# CtDSP_IO.net
KiCad netlist of a schematic drawn in Altium Designer
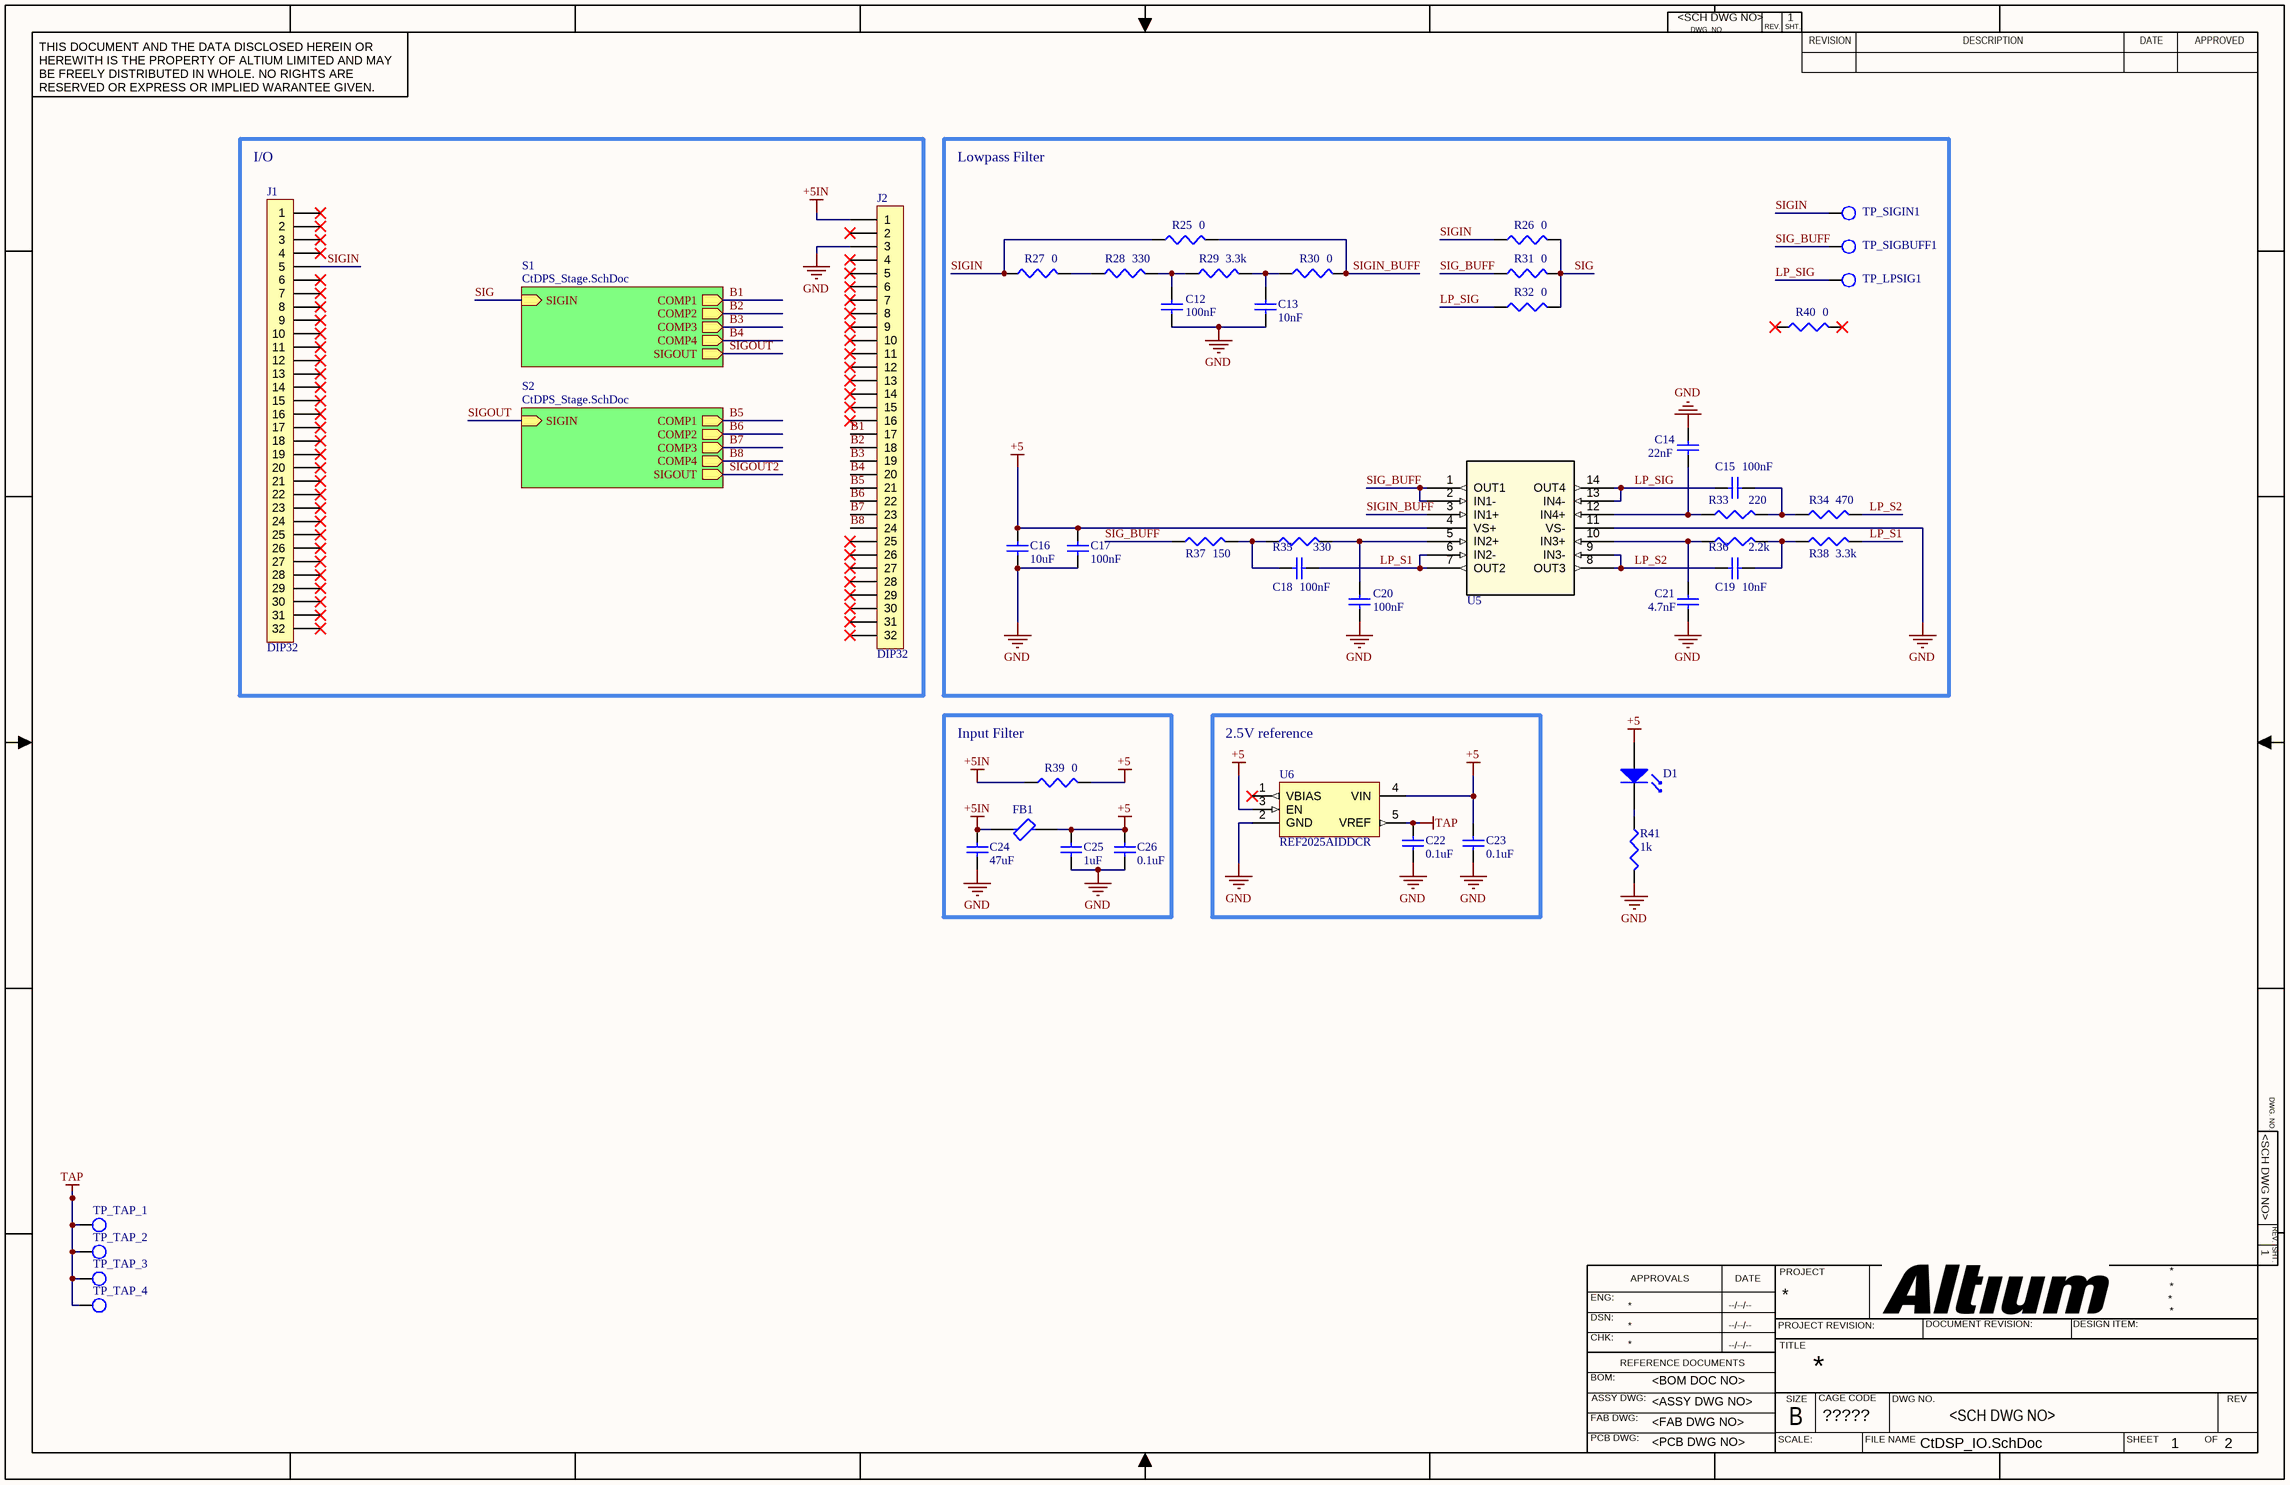
[diagram p0: CtDSP_IO.SchDoc]

(export (version "E")
  (design (tool "Eeschema 10.0.6"))
  (components
    (comp (ref "C12")
      (value "100nF")
      (footprint "C_0402")
      (fields (field (name "LCSC PART #") "C1525"))
      (libsource (lib "ctdsp") (part "C_0402"))
    )
    (comp (ref "C13")
      (value "10nF")
      (footprint "C_0402")
      (fields (field (name "LCSC PART #") "C15195"))
      (libsource (lib "ctdsp") (part "C_0402"))
    )
    (comp (ref "C14")
      (value "22nF")
      (footprint "C_0402")
      (fields (field (name "LCSC PART #") "C1532"))
      (libsource (lib "ctdsp") (part "C_0402"))
    )
    (comp (ref "C15")
      (value "100nF")
      (footprint "C_0402")
      (fields (field (name "LCSC PART #") "C1525"))
      (libsource (lib "ctdsp") (part "C_0402"))
    )
    (comp (ref "C16")
      (value "10uF")
      (footprint "C_0402")
      (fields (field (name "LCSC PART #") "C15525"))
      (libsource (lib "ctdsp") (part "C_0402"))
    )
    (comp (ref "C17")
      (value "100nF")
      (footprint "C_0402")
      (fields (field (name "LCSC PART #") "C1525"))
      (libsource (lib "ctdsp") (part "C_0402"))
    )
    (comp (ref "C18")
      (value "100nF")
      (footprint "C_0402")
      (fields (field (name "LCSC PART #") "C1525"))
      (libsource (lib "ctdsp") (part "C_0402"))
    )
    (comp (ref "C19")
      (value "10nF")
      (footprint "C_0402")
      (fields (field (name "LCSC PART #") "C15195"))
      (libsource (lib "ctdsp") (part "C_0402"))
    )
    (comp (ref "C20")
      (value "100nF")
      (footprint "C_0402")
      (fields (field (name "LCSC PART #") "C1525"))
      (libsource (lib "ctdsp") (part "C_0402"))
    )
    (comp (ref "C21")
      (value "4.7nF")
      (footprint "C_0402")
      (fields (field (name "LCSC PART #") "C1538"))
      (libsource (lib "ctdsp") (part "C_0402"))
    )
    (comp (ref "C22")
      (value "0.1uF")
      (footprint "C_0402")
      (fields (field (name "LCSC PART #") "C1525"))
      (libsource (lib "ctdsp") (part "C_0402"))
    )
    (comp (ref "C23")
      (value "0.1uF")
      (footprint "C_0402")
      (fields (field (name "LCSC PART #") "C1525"))
      (libsource (lib "ctdsp") (part "C_0402"))
    )
    (comp (ref "C24")
      (value "47uF")
      (footprint "C_0805")
      (fields (field (name "LCSC PART #") "C16780"))
      (libsource (lib "ctdsp") (part "C_0805"))
    )
    (comp (ref "C25")
      (value "1uF")
      (footprint "C_0603")
      (fields (field (name "LCSC PART #") "C15849"))
      (libsource (lib "ctdsp") (part "C_0603"))
    )
    (comp (ref "C26")
      (value "0.1uF")
      (footprint "C_0402")
      (fields (field (name "LCSC PART #") "C1525"))
      (libsource (lib "ctdsp") (part "C_0402"))
    )
    (comp (ref "D1")
      (value "LED_0603")
      (footprint "LED_6003")
      (fields (field (name "LCSC PART #") "C2286"))
      (libsource (lib "ctdsp") (part "LED_0603"))
    )
    (comp (ref "FB1")
      (value "BLM18PG121SN1D")
      (footprint "BLM18PG121SN1D")
      (description "-55℃~+125℃ 1 120Ω@100MHz 2A 50mΩ ±25% 0603 Ferrite Beads ROHS")
      (fields (field (name "LCSC PART #") "C14709"))
      (libsource (lib "ctdsp") (part "BLM18PG121SN1D"))
    )
    (comp (ref "J1") (value "DIP32") (footprint "DIP32") (libsource (lib "ctdsp") (part "DIP32")))
    (comp (ref "J2") (value "DIP32") (footprint "DIP32") (libsource (lib "") (part "DIP32_1")))
    (comp (ref "R25")
      (value "0")
      (footprint "RES_1206")
      (fields (field (name "LCSC PART #") "C17888"))
      (libsource (lib "ctdsp") (part "RES_1206"))
    )
    (comp (ref "R26")
      (value "0")
      (footprint "RES_1206")
      (fields (field (name "LCSC PART #") "C17888"))
      (libsource (lib "ctdsp") (part "RES_1206"))
    )
    (comp (ref "R27")
      (value "0")
      (footprint "RES_1206")
      (fields (field (name "LCSC PART #") "C17888"))
      (libsource (lib "ctdsp") (part "RES_1206"))
    )
    (comp (ref "R28")
      (value "330")
      (footprint "RES_0603")
      (fields (field (name "LCSC PART #") "C23138"))
      (libsource (lib "ctdsp") (part "RES_0603"))
    )
    (comp (ref "R29")
      (value "3.3k")
      (footprint "RES_0603")
      (fields (field (name "LCSC PART #") "C22978"))
      (libsource (lib "ctdsp") (part "RES_0603"))
    )
    (comp (ref "R30")
      (value "0")
      (footprint "RES_1206")
      (fields (field (name "LCSC PART #") "C17888"))
      (libsource (lib "ctdsp") (part "RES_1206"))
    )
    (comp (ref "R31")
      (value "0")
      (footprint "RES_1206")
      (fields (field (name "LCSC PART #") "C17888"))
      (libsource (lib "ctdsp") (part "RES_1206"))
    )
    (comp (ref "R32")
      (value "0")
      (footprint "RES_1206")
      (fields (field (name "LCSC PART #") "C17888"))
      (libsource (lib "ctdsp") (part "RES_1206"))
    )
    (comp (ref "R33")
      (value "220")
      (footprint "RES_0402")
      (fields (field (name "LCSC PART #") "C25091"))
      (libsource (lib "ctdsp") (part "RES_0402"))
    )
    (comp (ref "R34")
      (value "470")
      (footprint "RES_0402")
      (fields (field (name "LCSC PART #") "C25117"))
      (libsource (lib "ctdsp") (part "RES_0402"))
    )
    (comp (ref "R35")
      (value "330")
      (footprint "RES_0603")
      (fields (field (name "LCSC PART #") "C23138"))
      (libsource (lib "ctdsp") (part "RES_0603"))
    )
    (comp (ref "R36")
      (value "2.2k")
      (footprint "RES_0603")
      (fields (field (name "LCSC PART #") "C4190"))
      (libsource (lib "ctdsp") (part "RES_0603"))
    )
    (comp (ref "R37")
      (value "150")
      (footprint "RES_0603")
      (fields (field (name "LCSC PART #") "C22808"))
      (libsource (lib "ctdsp") (part "RES_0603"))
    )
    (comp (ref "R38")
      (value "3.3k")
      (footprint "RES_0603")
      (fields (field (name "LCSC PART #") "C22978"))
      (libsource (lib "ctdsp") (part "RES_0603"))
    )
    (comp (ref "R39")
      (value "0")
      (footprint "RES_1206")
      (fields (field (name "LCSC PART #") "C17888"))
      (libsource (lib "ctdsp") (part "RES_1206"))
    )
    (comp (ref "R40")
      (value "0")
      (footprint "RES_1206")
      (fields (field (name "LCSC PART #") "C17888"))
      (libsource (lib "ctdsp") (part "RES_1206"))
    )
    (comp (ref "R41")
      (value "1k")
      (footprint "RES_0402")
      (fields (field (name "LCSC PART #") "C11702"))
      (libsource (lib "ctdsp") (part "RES_0402"))
    )
    (comp (ref "TP_LPSIG1")
      (value "TESTPOINT")
      (footprint "TESTPOINT")
      (libsource (lib "ctdsp") (part "TESTPOINT"))
    )
    (comp (ref "TP_SIGBUFF1")
      (value "TESTPOINT")
      (footprint "TESTPOINT")
      (libsource (lib "ctdsp") (part "TESTPOINT"))
    )
    (comp (ref "TP_SIGIN1")
      (value "TESTPOINT")
      (footprint "TESTPOINT")
      (libsource (lib "ctdsp") (part "TESTPOINT"))
    )
    (comp (ref "TP_TAP_1")
      (value "TESTPOINT")
      (footprint "TESTPOINT")
      (libsource (lib "ctdsp") (part "TESTPOINT"))
    )
    (comp (ref "TP_TAP_2")
      (value "TESTPOINT")
      (footprint "TESTPOINT")
      (libsource (lib "ctdsp") (part "TESTPOINT"))
    )
    (comp (ref "TP_TAP_3")
      (value "TESTPOINT")
      (footprint "TESTPOINT")
      (libsource (lib "ctdsp") (part "TESTPOINT"))
    )
    (comp (ref "TP_TAP_4")
      (value "TP_TAP_4")
      (footprint "TESTPOINT")
      (libsource (lib "ctdsp") (part "TESTPOINT"))
    )
    (comp (ref "U5")
      (value "ADA4891-4ARZ-R7")
      (footprint "ADA4891-4ARZ-R7")
      (description "Quad Rail-to-Rail Op-Amp, 240 MHz, 170 V/µs, SOT-23-5")
      (fields (field (name "LCSC PART #") "C654290"))
      (libsource (lib "ctdsp") (part "ADA4891-4ARZ-R7"))
    )
    (comp (ref "U6")
      (value "REF2025AIDDCR")
      (footprint "REF2025AIDDCR")
      (fields (field (name "LCSC PART #") "C962078"))
      (libsource (lib "ctdsp") (part "REF2025AIDDCR"))
    )
  )
  (nets
    (net (code "1") (name "+5") (class "Default")
      (node (ref "C16") (pin "1") (pinfunction "1_1") (pintype "passive"))
      (node (ref "C17") (pin "2") (pinfunction "2_2") (pintype "passive"))
      (node (ref "C23") (pin "1") (pinfunction "1_1") (pintype "passive"))
      (node (ref "C25") (pin "2") (pinfunction "2_2") (pintype "passive"))
      (node (ref "C26") (pin "1") (pinfunction "1_1") (pintype "passive"))
      (node (ref "D1") (pin "2") (pinfunction "K_2") (pintype "passive"))
      (node (ref "FB1") (pin "2") (pinfunction "2_2") (pintype "passive"))
      (node (ref "R39") (pin "2") (pinfunction "2_2") (pintype "passive"))
      (node (ref "U5") (pin "4") (pinfunction "VS+_4") (pintype "power_in"))
      (node (ref "U6") (pin "3") (pinfunction "EN_3") (pintype "input"))
      (node (ref "U6") (pin "4") (pinfunction "VIN_4") (pintype "power_in"))
    )
    (net (code "2") (name "+5IN") (class "Default")
      (node (ref "C24") (pin "2") (pinfunction "2_2") (pintype "passive"))
      (node (ref "FB1") (pin "1") (pinfunction "1_1") (pintype "passive"))
      (node (ref "J2") (pin "1") (pinfunction "1_1") (pintype "passive"))
      (node (ref "R39") (pin "1") (pinfunction "1_1") (pintype "passive"))
    )
    (net (code "3") (name "/B1") (class "Default")
      (node (ref "J2") (pin "17") (pinfunction "17_17") (pintype "passive"))
    )
    (net (code "4") (name "/B2") (class "Default")
      (node (ref "J2") (pin "18") (pinfunction "18_18") (pintype "passive"))
    )
    (net (code "5") (name "/B3") (class "Default")
      (node (ref "J2") (pin "19") (pinfunction "19_19") (pintype "passive"))
    )
    (net (code "6") (name "/B4") (class "Default")
      (node (ref "J2") (pin "20") (pinfunction "20_20") (pintype "passive"))
    )
    (net (code "7") (name "/B5") (class "Default")
      (node (ref "J2") (pin "21") (pinfunction "21_21") (pintype "passive"))
    )
    (net (code "8") (name "/B6") (class "Default")
      (node (ref "J2") (pin "22") (pinfunction "22_22") (pintype "passive"))
    )
    (net (code "9") (name "/B7") (class "Default")
      (node (ref "J2") (pin "23") (pinfunction "23_23") (pintype "passive"))
    )
    (net (code "10") (name "/B8") (class "Default")
      (node (ref "J2") (pin "24") (pinfunction "24_24") (pintype "passive"))
    )
    (net (code "11") (name "/LP_S1") (class "Default")
      (node (ref "C18") (pin "1") (pinfunction "1_1") (pintype "passive"))
      (node (ref "R38") (pin "2") (pinfunction "2_2") (pintype "passive"))
      (node (ref "U5") (pin "6") (pinfunction "IN2-_6") (pintype "input"))
      (node (ref "U5") (pin "7") (pinfunction "OUT2_7") (pintype "output"))
    )
    (net (code "12") (name "/LP_S2") (class "Default")
      (node (ref "C19") (pin "1") (pinfunction "1_1") (pintype "passive"))
      (node (ref "R34") (pin "2") (pinfunction "2_2") (pintype "passive"))
      (node (ref "U5") (pin "8") (pinfunction "OUT3_8") (pintype "output"))
      (node (ref "U5") (pin "9") (pinfunction "IN3-_9") (pintype "input"))
    )
    (net (code "13") (name "/LP_SIG") (class "Default")
      (node (ref "C15") (pin "2") (pinfunction "2_2") (pintype "passive"))
      (node (ref "R32") (pin "1") (pinfunction "1_1") (pintype "passive"))
      (node (ref "TP_LPSIG1") (pin "1") (pinfunction "1_1") (pintype "passive"))
      (node (ref "U5") (pin "13") (pinfunction "IN4-_13") (pintype "input"))
      (node (ref "U5") (pin "14") (pinfunction "OUT4_14") (pintype "output"))
    )
    (net (code "14") (name "/SIG") (class "Default")
      (node (ref "R26") (pin "2") (pinfunction "2_2") (pintype "passive"))
      (node (ref "R31") (pin "2") (pinfunction "2_2") (pintype "passive"))
      (node (ref "R32") (pin "2") (pinfunction "2_2") (pintype "passive"))
    )
    (net (code "15") (name "/SIGIN") (class "Default")
      (node (ref "J1") (pin "5") (pinfunction "5_5") (pintype "passive"))
      (node (ref "R25") (pin "1") (pinfunction "1_1") (pintype "passive"))
      (node (ref "R26") (pin "1") (pinfunction "1_1") (pintype "passive"))
      (node (ref "R27") (pin "1") (pinfunction "1_1") (pintype "passive"))
      (node (ref "TP_SIGIN1") (pin "1") (pinfunction "1_1") (pintype "passive"))
    )
    (net (code "16") (name "/SIGIN_BUFF") (class "Default")
      (node (ref "R25") (pin "2") (pinfunction "2_2") (pintype "passive"))
      (node (ref "R30") (pin "2") (pinfunction "2_2") (pintype "passive"))
      (node (ref "U5") (pin "3") (pinfunction "IN1+_3") (pintype "input"))
    )
    (net (code "19") (name "/SIG_BUFF") (class "Default")
      (node (ref "R31") (pin "1") (pinfunction "1_1") (pintype "passive"))
      (node (ref "R37") (pin "1") (pinfunction "1_1") (pintype "passive"))
      (node (ref "TP_SIGBUFF1") (pin "1") (pinfunction "1_1") (pintype "passive"))
      (node (ref "U5") (pin "1") (pinfunction "OUT1_1") (pintype "output"))
      (node (ref "U5") (pin "2") (pinfunction "IN1-_2") (pintype "input"))
    )
    (net (code "20") (name "GND") (class "Default")
      (node (ref "C12") (pin "1") (pinfunction "1_1") (pintype "passive"))
      (node (ref "C13") (pin "1") (pinfunction "1_1") (pintype "passive"))
      (node (ref "C14") (pin "2") (pinfunction "2_2") (pintype "passive"))
      (node (ref "C16") (pin "2") (pinfunction "2_2") (pintype "passive"))
      (node (ref "C17") (pin "1") (pinfunction "1_1") (pintype "passive"))
      (node (ref "C20") (pin "1") (pinfunction "1_1") (pintype "passive"))
      (node (ref "C21") (pin "1") (pinfunction "1_1") (pintype "passive"))
      (node (ref "C22") (pin "2") (pinfunction "2_2") (pintype "passive"))
      (node (ref "C23") (pin "2") (pinfunction "2_2") (pintype "passive"))
      (node (ref "C24") (pin "1") (pinfunction "1_1") (pintype "passive"))
      (node (ref "C25") (pin "1") (pinfunction "1_1") (pintype "passive"))
      (node (ref "C26") (pin "2") (pinfunction "2_2") (pintype "passive"))
      (node (ref "J2") (pin "3") (pinfunction "3_3") (pintype "passive"))
      (node (ref "R41") (pin "2") (pinfunction "2_2") (pintype "passive"))
      (node (ref "U5") (pin "11") (pinfunction "VS-_11") (pintype "power_in"))
      (node (ref "U6") (pin "2") (pinfunction "GND_2") (pintype "power_in"))
    )
    (net (code "21") (name "Net-(C12-Pad2)") (class "Default")
      (node (ref "C12") (pin "2") (pinfunction "2_2") (pintype "passive"))
      (node (ref "R28") (pin "2") (pinfunction "2_2") (pintype "passive"))
      (node (ref "R29") (pin "1") (pinfunction "1_1") (pintype "passive"))
    )
    (net (code "22") (name "Net-(C13-Pad2)") (class "Default")
      (node (ref "C13") (pin "2") (pinfunction "2_2") (pintype "passive"))
      (node (ref "R29") (pin "2") (pinfunction "2_2") (pintype "passive"))
      (node (ref "R30") (pin "1") (pinfunction "1_1") (pintype "passive"))
    )
    (net (code "23") (name "Net-(C15-Pad1)") (class "Default")
      (node (ref "C15") (pin "1") (pinfunction "1_1") (pintype "passive"))
      (node (ref "R33") (pin "2") (pinfunction "2_2") (pintype "passive"))
      (node (ref "R34") (pin "1") (pinfunction "1_1") (pintype "passive"))
    )
    (net (code "24") (name "Net-(C18-Pad2)") (class "Default")
      (node (ref "C18") (pin "2") (pinfunction "2_2") (pintype "passive"))
      (node (ref "R35") (pin "1") (pinfunction "1_1") (pintype "passive"))
      (node (ref "R37") (pin "2") (pinfunction "2_2") (pintype "passive"))
    )
    (net (code "25") (name "Net-(C19-Pad2)") (class "Default")
      (node (ref "C19") (pin "2") (pinfunction "2_2") (pintype "passive"))
      (node (ref "R36") (pin "2") (pinfunction "2_2") (pintype "passive"))
      (node (ref "R38") (pin "1") (pinfunction "1_1") (pintype "passive"))
    )
    (net (code "26") (name "Net-(D1-A)") (class "Default")
      (node (ref "D1") (pin "1") (pinfunction "A_1") (pintype "passive"))
      (node (ref "R41") (pin "1") (pinfunction "1_1") (pintype "passive"))
    )
    (net (code "27") (name "Net-(R27-Pad2)") (class "Default")
      (node (ref "R27") (pin "2") (pinfunction "2_2") (pintype "passive"))
      (node (ref "R28") (pin "1") (pinfunction "1_1") (pintype "passive"))
    )
    (net (code "28") (name "Net-(U5-IN2+)") (class "Default")
      (node (ref "C20") (pin "2") (pinfunction "2_2") (pintype "passive"))
      (node (ref "R35") (pin "2") (pinfunction "2_2") (pintype "passive"))
      (node (ref "U5") (pin "5") (pinfunction "IN2+_5") (pintype "input"))
    )
    (net (code "29") (name "Net-(U5-IN3+)") (class "Default")
      (node (ref "C21") (pin "2") (pinfunction "2_2") (pintype "passive"))
      (node (ref "R36") (pin "1") (pinfunction "1_1") (pintype "passive"))
      (node (ref "U5") (pin "10") (pinfunction "IN3+_10") (pintype "input"))
    )
    (net (code "30") (name "Net-(U5-IN4+)") (class "Default")
      (node (ref "C14") (pin "1") (pinfunction "1_1") (pintype "passive"))
      (node (ref "R33") (pin "1") (pinfunction "1_1") (pintype "passive"))
      (node (ref "U5") (pin "12") (pinfunction "IN4+_12") (pintype "input"))
    )
    (net (code "31") (name "TAP") (class "Default")
      (node (ref "C22") (pin "1") (pinfunction "1_1") (pintype "passive"))
      (node (ref "TP_TAP_1") (pin "1") (pinfunction "1_1") (pintype "passive"))
      (node (ref "TP_TAP_2") (pin "1") (pinfunction "1_1") (pintype "passive"))
      (node (ref "TP_TAP_3") (pin "1") (pinfunction "1_1") (pintype "passive"))
      (node (ref "TP_TAP_4") (pin "1") (pinfunction "1_1") (pintype "passive"))
      (node (ref "U6") (pin "5") (pinfunction "VREF_5") (pintype "output"))
    )
    (net (code "32") (name "unconnected-(J1-Pad1)") (class "Default")
      (node (ref "J1") (pin "1") (pinfunction "1_1") (pintype "passive+no_connect"))
    )
    (net (code "33") (name "unconnected-(J1-Pad2)") (class "Default")
      (node (ref "J1") (pin "2") (pinfunction "2_2") (pintype "passive+no_connect"))
    )
    (net (code "34") (name "unconnected-(J1-Pad3)") (class "Default")
      (node (ref "J1") (pin "3") (pinfunction "3_3") (pintype "passive+no_connect"))
    )
    (net (code "35") (name "unconnected-(J1-Pad4)") (class "Default")
      (node (ref "J1") (pin "4") (pinfunction "4_4") (pintype "passive+no_connect"))
    )
    (net (code "36") (name "unconnected-(J1-Pad6)") (class "Default")
      (node (ref "J1") (pin "6") (pinfunction "6_6") (pintype "passive+no_connect"))
    )
    (net (code "37") (name "unconnected-(J1-Pad7)") (class "Default")
      (node (ref "J1") (pin "7") (pinfunction "7_7") (pintype "passive+no_connect"))
    )
    (net (code "38") (name "unconnected-(J1-Pad8)") (class "Default")
      (node (ref "J1") (pin "8") (pinfunction "8_8") (pintype "passive+no_connect"))
    )
    (net (code "39") (name "unconnected-(J1-Pad9)") (class "Default")
      (node (ref "J1") (pin "9") (pinfunction "9_9") (pintype "passive+no_connect"))
    )
    (net (code "40") (name "unconnected-(J1-Pad10)") (class "Default")
      (node (ref "J1") (pin "10") (pinfunction "10_10") (pintype "passive+no_connect"))
    )
    (net (code "41") (name "unconnected-(J1-Pad11)") (class "Default")
      (node (ref "J1") (pin "11") (pinfunction "11_11") (pintype "passive+no_connect"))
    )
    (net (code "42") (name "unconnected-(J1-Pad12)") (class "Default")
      (node (ref "J1") (pin "12") (pinfunction "12_12") (pintype "passive+no_connect"))
    )
    (net (code "43") (name "unconnected-(J1-Pad13)") (class "Default")
      (node (ref "J1") (pin "13") (pinfunction "13_13") (pintype "passive+no_connect"))
    )
    (net (code "44") (name "unconnected-(J1-Pad14)") (class "Default")
      (node (ref "J1") (pin "14") (pinfunction "14_14") (pintype "passive+no_connect"))
    )
    (net (code "45") (name "unconnected-(J1-Pad15)") (class "Default")
      (node (ref "J1") (pin "15") (pinfunction "15_15") (pintype "passive+no_connect"))
    )
    (net (code "46") (name "unconnected-(J1-Pad16)") (class "Default")
      (node (ref "J1") (pin "16") (pinfunction "16_16") (pintype "passive+no_connect"))
    )
    (net (code "47") (name "unconnected-(J1-Pad17)") (class "Default")
      (node (ref "J1") (pin "17") (pinfunction "17_17") (pintype "passive+no_connect"))
    )
    (net (code "48") (name "unconnected-(J1-Pad18)") (class "Default")
      (node (ref "J1") (pin "18") (pinfunction "18_18") (pintype "passive+no_connect"))
    )
    (net (code "49") (name "unconnected-(J1-Pad19)") (class "Default")
      (node (ref "J1") (pin "19") (pinfunction "19_19") (pintype "passive+no_connect"))
    )
    (net (code "50") (name "unconnected-(J1-Pad20)") (class "Default")
      (node (ref "J1") (pin "20") (pinfunction "20_20") (pintype "passive+no_connect"))
    )
    (net (code "51") (name "unconnected-(J1-Pad21)") (class "Default")
      (node (ref "J1") (pin "21") (pinfunction "21_21") (pintype "passive+no_connect"))
    )
    (net (code "52") (name "unconnected-(J1-Pad22)") (class "Default")
      (node (ref "J1") (pin "22") (pinfunction "22_22") (pintype "passive+no_connect"))
    )
    (net (code "53") (name "unconnected-(J1-Pad23)") (class "Default")
      (node (ref "J1") (pin "23") (pinfunction "23_23") (pintype "passive+no_connect"))
    )
    (net (code "54") (name "unconnected-(J1-Pad24)") (class "Default")
      (node (ref "J1") (pin "24") (pinfunction "24_24") (pintype "passive+no_connect"))
    )
    (net (code "55") (name "unconnected-(J1-Pad25)") (class "Default")
      (node (ref "J1") (pin "25") (pinfunction "25_25") (pintype "passive+no_connect"))
    )
    (net (code "56") (name "unconnected-(J1-Pad26)") (class "Default")
      (node (ref "J1") (pin "26") (pinfunction "26_26") (pintype "passive+no_connect"))
    )
    (net (code "57") (name "unconnected-(J1-Pad27)") (class "Default")
      (node (ref "J1") (pin "27") (pinfunction "27_27") (pintype "passive+no_connect"))
    )
    (net (code "58") (name "unconnected-(J1-Pad28)") (class "Default")
      (node (ref "J1") (pin "28") (pinfunction "28_28") (pintype "passive+no_connect"))
    )
    (net (code "59") (name "unconnected-(J1-Pad29)") (class "Default")
      (node (ref "J1") (pin "29") (pinfunction "29_29") (pintype "passive+no_connect"))
    )
    (net (code "60") (name "unconnected-(J1-Pad30)") (class "Default")
      (node (ref "J1") (pin "30") (pinfunction "30_30") (pintype "passive+no_connect"))
    )
    (net (code "61") (name "unconnected-(J1-Pad31)") (class "Default")
      (node (ref "J1") (pin "31") (pinfunction "31_31") (pintype "passive+no_connect"))
    )
    (net (code "62") (name "unconnected-(J1-Pad32)") (class "Default")
      (node (ref "J1") (pin "32") (pinfunction "32_32") (pintype "passive+no_connect"))
    )
    (net (code "63") (name "unconnected-(J2-Pad2)") (class "Default")
      (node (ref "J2") (pin "2") (pinfunction "2_2") (pintype "passive+no_connect"))
    )
    (net (code "64") (name "unconnected-(J2-Pad4)") (class "Default")
      (node (ref "J2") (pin "4") (pinfunction "4_4") (pintype "passive+no_connect"))
    )
    (net (code "65") (name "unconnected-(J2-Pad5)") (class "Default")
      (node (ref "J2") (pin "5") (pinfunction "5_5") (pintype "passive+no_connect"))
    )
    (net (code "66") (name "unconnected-(J2-Pad6)") (class "Default")
      (node (ref "J2") (pin "6") (pinfunction "6_6") (pintype "passive+no_connect"))
    )
    (net (code "67") (name "unconnected-(J2-Pad7)") (class "Default")
      (node (ref "J2") (pin "7") (pinfunction "7_7") (pintype "passive+no_connect"))
    )
    (net (code "68") (name "unconnected-(J2-Pad8)") (class "Default")
      (node (ref "J2") (pin "8") (pinfunction "8_8") (pintype "passive+no_connect"))
    )
    (net (code "69") (name "unconnected-(J2-Pad9)") (class "Default")
      (node (ref "J2") (pin "9") (pinfunction "9_9") (pintype "passive+no_connect"))
    )
    (net (code "70") (name "unconnected-(J2-Pad10)") (class "Default")
      (node (ref "J2") (pin "10") (pinfunction "10_10") (pintype "passive+no_connect"))
    )
    (net (code "71") (name "unconnected-(J2-Pad11)") (class "Default")
      (node (ref "J2") (pin "11") (pinfunction "11_11") (pintype "passive+no_connect"))
    )
    (net (code "72") (name "unconnected-(J2-Pad12)") (class "Default")
      (node (ref "J2") (pin "12") (pinfunction "12_12") (pintype "passive+no_connect"))
    )
    (net (code "73") (name "unconnected-(J2-Pad13)") (class "Default")
      (node (ref "J2") (pin "13") (pinfunction "13_13") (pintype "passive+no_connect"))
    )
    (net (code "74") (name "unconnected-(J2-Pad14)") (class "Default")
      (node (ref "J2") (pin "14") (pinfunction "14_14") (pintype "passive+no_connect"))
    )
    (net (code "75") (name "unconnected-(J2-Pad15)") (class "Default")
      (node (ref "J2") (pin "15") (pinfunction "15_15") (pintype "passive+no_connect"))
    )
    (net (code "76") (name "unconnected-(J2-Pad16)") (class "Default")
      (node (ref "J2") (pin "16") (pinfunction "16_16") (pintype "passive+no_connect"))
    )
    (net (code "77") (name "unconnected-(J2-Pad25)") (class "Default")
      (node (ref "J2") (pin "25") (pinfunction "25_25") (pintype "passive+no_connect"))
    )
    (net (code "78") (name "unconnected-(J2-Pad26)") (class "Default")
      (node (ref "J2") (pin "26") (pinfunction "26_26") (pintype "passive+no_connect"))
    )
    (net (code "79") (name "unconnected-(J2-Pad27)") (class "Default")
      (node (ref "J2") (pin "27") (pinfunction "27_27") (pintype "passive+no_connect"))
    )
    (net (code "80") (name "unconnected-(J2-Pad28)") (class "Default")
      (node (ref "J2") (pin "28") (pinfunction "28_28") (pintype "passive+no_connect"))
    )
    (net (code "81") (name "unconnected-(J2-Pad29)") (class "Default")
      (node (ref "J2") (pin "29") (pinfunction "29_29") (pintype "passive+no_connect"))
    )
    (net (code "82") (name "unconnected-(J2-Pad30)") (class "Default")
      (node (ref "J2") (pin "30") (pinfunction "30_30") (pintype "passive+no_connect"))
    )
    (net (code "83") (name "unconnected-(J2-Pad31)") (class "Default")
      (node (ref "J2") (pin "31") (pinfunction "31_31") (pintype "passive+no_connect"))
    )
    (net (code "84") (name "unconnected-(J2-Pad32)") (class "Default")
      (node (ref "J2") (pin "32") (pinfunction "32_32") (pintype "passive+no_connect"))
    )
    (net (code "85") (name "unconnected-(R40-Pad1)") (class "Default")
      (node (ref "R40") (pin "1") (pinfunction "1_1") (pintype "passive+no_connect"))
    )
    (net (code "86") (name "unconnected-(R40-Pad2)") (class "Default")
      (node (ref "R40") (pin "2") (pinfunction "2_2") (pintype "passive+no_connect"))
    )
    (net (code "87") (name "unconnected-(U6-VBIAS-Pad1)") (class "Default")
      (node (ref "U6") (pin "1") (pinfunction "VBIAS_1") (pintype "output+no_connect"))
    )
  )
)
